# SHDN-IMD-S05-V00-IsolatedCAN.net
KiCad netlist of a schematic drawn in Altium Designer
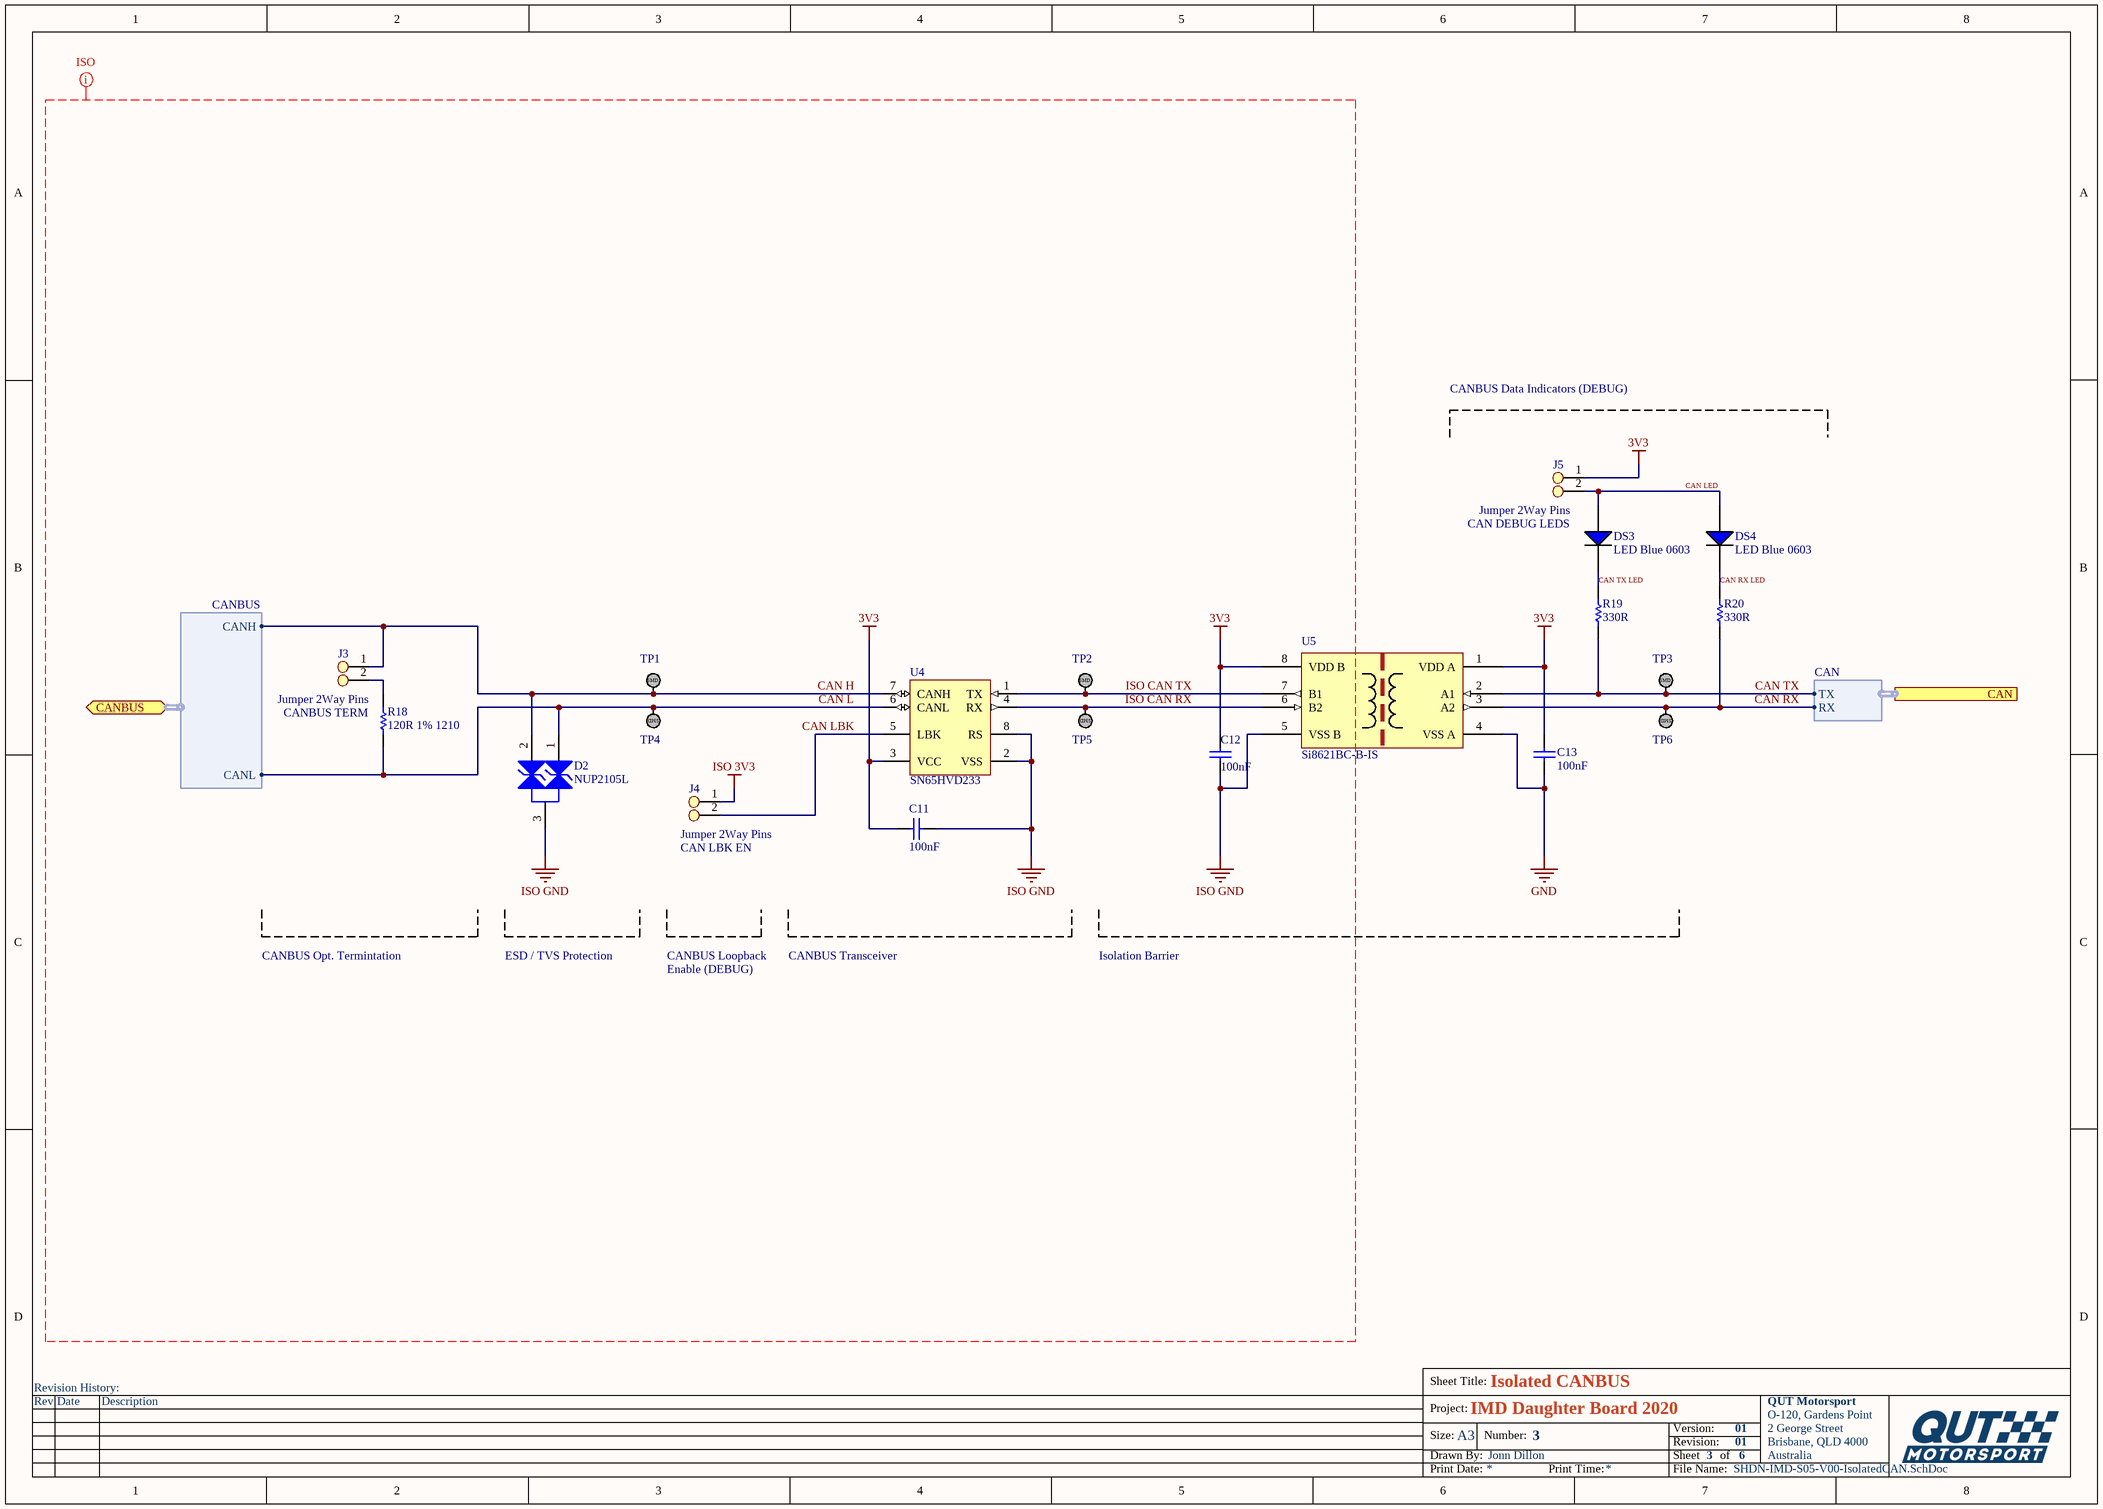
[diagram p0: SHDN-IMD-S05-V00-IsolatedCAN.SchDoc]

(export (version "E")
  (design (tool "Eeschema 10.0.6"))
  (components
    (comp (ref "C11")
      (value "100nF")
      (footprint "Cap_Ceramic_0603")
      (description "Capacitor, Ceramic, SMD, 100nF, 100V, 5%, X7R, 0603")
      (libsource (lib "StandardCapacitors") (part "100nF 100V 5% X7R 0603"))
    )
    (comp (ref "C12")
      (value "100nF")
      (footprint "Cap_Ceramic_0603")
      (description "Capacitor, Ceramic, SMD, 100nF, 100V, 5%, X7R, 0603")
      (libsource (lib "StandardCapacitors") (part "100nF 100V 5% X7R 0603"))
    )
    (comp (ref "C13")
      (value "100nF")
      (footprint "Cap_Ceramic_0603")
      (description "Capacitor, Ceramic, SMD, 100nF, 100V, 5%, X7R, 0603")
      (libsource (lib "StandardCapacitors") (part "100nF 100V 5% X7R 0603"))
    )
    (comp (ref "D2")
      (value "NUP2105L")
      (footprint "NUP2105L")
      (libsource (lib "QUTMS_CANLibrary") (part "NUP2105L"))
    )
    (comp (ref "DS3")
      (value "LED Blue 0603")
      (footprint "LED BLUE 0603")
      (libsource (lib "QUTMS_LEDLibrary") (part "LED BLUE 0603"))
    )
    (comp (ref "DS4")
      (value "LED Blue 0603")
      (footprint "LED BLUE 0603")
      (libsource (lib "QUTMS_LEDLibrary") (part "LED BLUE 0603"))
    )
    (comp (ref "J3")
      (value "Jumper 2Way Pins")
      (footprint "Jumper_2Way_Pin")
      (description "Jumper 2Way Side Pins")
      (libsource (lib "QUTMS_JumperLibrary") (part "Jumper 2Way Side Pins"))
    )
    (comp (ref "J4")
      (value "Jumper 2Way Pins")
      (footprint "Jumper_2Way_Pin")
      (description "Jumper 2Way Side Pins")
      (libsource (lib "QUTMS_JumperLibrary") (part "Jumper 2Way Side Pins"))
    )
    (comp (ref "J5")
      (value "Jumper 2Way Pins")
      (footprint "Jumper_2Way_Pin")
      (description "Jumper 2Way Side Pins")
      (libsource (lib "QUTMS_JumperLibrary") (part "Jumper 2Way Side Pins"))
    )
    (comp (ref "R18")
      (value "120R 1% 1210")
      (footprint "Res_ThinFilm_1210")
      (description "Resistor, SMD, 120R, 0.25W, 1%, 1210")
      (libsource (lib "StandardResistors") (part "120R 1% 1210"))
    )
    (comp (ref "R19")
      (value "330R")
      (footprint "Res_ThinFilm_0603")
      (description "Resistor, SMD, 330R, 0.1W, 5%, 0603")
      (libsource (lib "StandardResistors") (part "330R 5% 0603"))
    )
    (comp (ref "R20")
      (value "330R")
      (footprint "Res_ThinFilm_0603")
      (description "Resistor, SMD, 330R, 0.1W, 5%, 0603")
      (libsource (lib "StandardResistors") (part "330R 5% 0603"))
    )
    (comp (ref "TP1")
      (value "TestPoint_SMD")
      (footprint "TestPointSMD")
      (libsource (lib "StandardTest") (part "TestPoint_SMD"))
    )
    (comp (ref "TP2")
      (value "TestPoint_SMD")
      (footprint "TestPointSMD")
      (libsource (lib "StandardTest") (part "TestPoint_SMD"))
    )
    (comp (ref "TP3")
      (value "TestPoint_SMD")
      (footprint "TestPointSMD")
      (libsource (lib "StandardTest") (part "TestPoint_SMD"))
    )
    (comp (ref "TP4")
      (value "TestPoint_SMD")
      (footprint "TestPointSMD")
      (libsource (lib "StandardTest") (part "TestPoint_SMD"))
    )
    (comp (ref "TP5")
      (value "TestPoint_SMD")
      (footprint "TestPointSMD")
      (libsource (lib "StandardTest") (part "TestPoint_SMD"))
    )
    (comp (ref "TP6")
      (value "TestPoint_SMD")
      (footprint "TestPointSMD")
      (libsource (lib "StandardTest") (part "TestPoint_SMD"))
    )
    (comp (ref "U4")
      (value "SN65HVD233")
      (footprint "SN65HVD233DR")
      (libsource (lib "QUTMS_CANLibrary") (part "SN65HVD233"))
    )
    (comp (ref "U5")
      (value "Si8621BC-B-IS")
      (footprint "Si8621BC-B-IS")
      (libsource (lib "QUTMS_IsolatorLibrary") (part "Si8621BC-B-IS"))
    )
  )
  (nets
    (net (code "3") (name "/CAN H") (class "Default")
      (node (ref "D2") (pin "2") (pinfunction "2_2") (pintype "passive"))
      (node (ref "J3") (pin "1") (pinfunction "1_1") (pintype "passive"))
      (node (ref "TP1") (pin "1") (pinfunction "1_1") (pintype "passive"))
      (node (ref "U4") (pin "7") (pinfunction "CANH_7") (pintype "bidirectional"))
    )
    (net (code "4") (name "/CAN L") (class "Default")
      (node (ref "D2") (pin "1") (pinfunction "1_1") (pintype "passive"))
      (node (ref "R18") (pin "1") (pinfunction "1_1") (pintype "passive"))
      (node (ref "TP4") (pin "1") (pinfunction "1_1") (pintype "passive"))
      (node (ref "U4") (pin "6") (pinfunction "CANL_6") (pintype "bidirectional"))
    )
    (net (code "5") (name "/CAN LBK") (class "Default")
      (node (ref "J4") (pin "2") (pinfunction "2_2") (pintype "passive"))
      (node (ref "U4") (pin "5") (pinfunction "LBK_5") (pintype "passive"))
    )
    (net (code "6") (name "/CAN LED") (class "Default")
      (node (ref "DS3") (pin "1") (pinfunction "A_1") (pintype "passive"))
      (node (ref "DS4") (pin "1") (pinfunction "A_1") (pintype "passive"))
      (node (ref "J5") (pin "2") (pinfunction "2_2") (pintype "passive"))
    )
    (net (code "7") (name "/CAN RX") (class "Default")
      (node (ref "R20") (pin "1") (pinfunction "1_1") (pintype "passive"))
      (node (ref "TP6") (pin "1") (pinfunction "1_1") (pintype "passive"))
      (node (ref "U5") (pin "3") (pinfunction "A2_3") (pintype "output"))
    )
    (net (code "8") (name "/CAN RX LED") (class "Default")
      (node (ref "DS4") (pin "2") (pinfunction "C_2") (pintype "passive"))
      (node (ref "R20") (pin "2") (pinfunction "2_2") (pintype "passive"))
    )
    (net (code "9") (name "/CAN TX") (class "Default")
      (node (ref "R19") (pin "1") (pinfunction "1_1") (pintype "passive"))
      (node (ref "TP3") (pin "1") (pinfunction "1_1") (pintype "passive"))
      (node (ref "U5") (pin "2") (pinfunction "A1_2") (pintype "input"))
    )
    (net (code "10") (name "/CAN TX LED") (class "Default")
      (node (ref "DS3") (pin "2") (pinfunction "C_2") (pintype "passive"))
      (node (ref "R19") (pin "2") (pinfunction "2_2") (pintype "passive"))
    )
    (net (code "11") (name "/ISO CAN RX") (class "Default")
      (node (ref "TP5") (pin "1") (pinfunction "1_1") (pintype "passive"))
      (node (ref "U4") (pin "4") (pinfunction "RX_4") (pintype "output"))
      (node (ref "U5") (pin "6") (pinfunction "B2_6") (pintype "input"))
    )
    (net (code "12") (name "/ISO CAN TX") (class "Default")
      (node (ref "TP2") (pin "1") (pinfunction "1_1") (pintype "passive"))
      (node (ref "U4") (pin "1") (pinfunction "TX_1") (pintype "input"))
      (node (ref "U5") (pin "7") (pinfunction "B1_7") (pintype "output"))
    )
    (net (code "15") (name "3V3") (class "Default")
      (node (ref "C11") (pin "1") (pinfunction "1_1") (pintype "passive"))
      (node (ref "C12") (pin "2") (pinfunction "2_2") (pintype "passive"))
      (node (ref "C13") (pin "2") (pinfunction "2_2") (pintype "passive"))
      (node (ref "J5") (pin "1") (pinfunction "1_1") (pintype "passive"))
      (node (ref "U4") (pin "3") (pinfunction "VCC_3") (pintype "passive"))
      (node (ref "U5") (pin "1") (pinfunction "VDD_A_1") (pintype "passive"))
      (node (ref "U5") (pin "8") (pinfunction "VDD_B_8") (pintype "passive"))
    )
    (net (code "16") (name "GND") (class "Default")
      (node (ref "C13") (pin "1") (pinfunction "1_1") (pintype "passive"))
      (node (ref "U5") (pin "4") (pinfunction "VSS_A_4") (pintype "passive"))
    )
    (net (code "17") (name "ISO 3V3") (class "Default")
      (node (ref "J4") (pin "1") (pinfunction "1_1") (pintype "passive"))
    )
    (net (code "18") (name "ISO GND") (class "Default")
      (node (ref "C11") (pin "2") (pinfunction "2_2") (pintype "passive"))
      (node (ref "C12") (pin "1") (pinfunction "1_1") (pintype "passive"))
      (node (ref "D2") (pin "3") (pinfunction "3_3") (pintype "passive"))
      (node (ref "U4") (pin "2") (pinfunction "VSS_2") (pintype "passive"))
      (node (ref "U4") (pin "8") (pinfunction "RS_8") (pintype "passive"))
      (node (ref "U5") (pin "5") (pinfunction "VSS_B_5") (pintype "passive"))
    )
    (net (code "19") (name "Net-(J3-Pad2)") (class "Default")
      (node (ref "J3") (pin "2") (pinfunction "2_2") (pintype "passive"))
      (node (ref "R18") (pin "2") (pinfunction "2_2") (pintype "passive"))
    )
  )
)
